# r10_0_328_1284.net
KiCad netlist of a schematic drawn in EAGLE
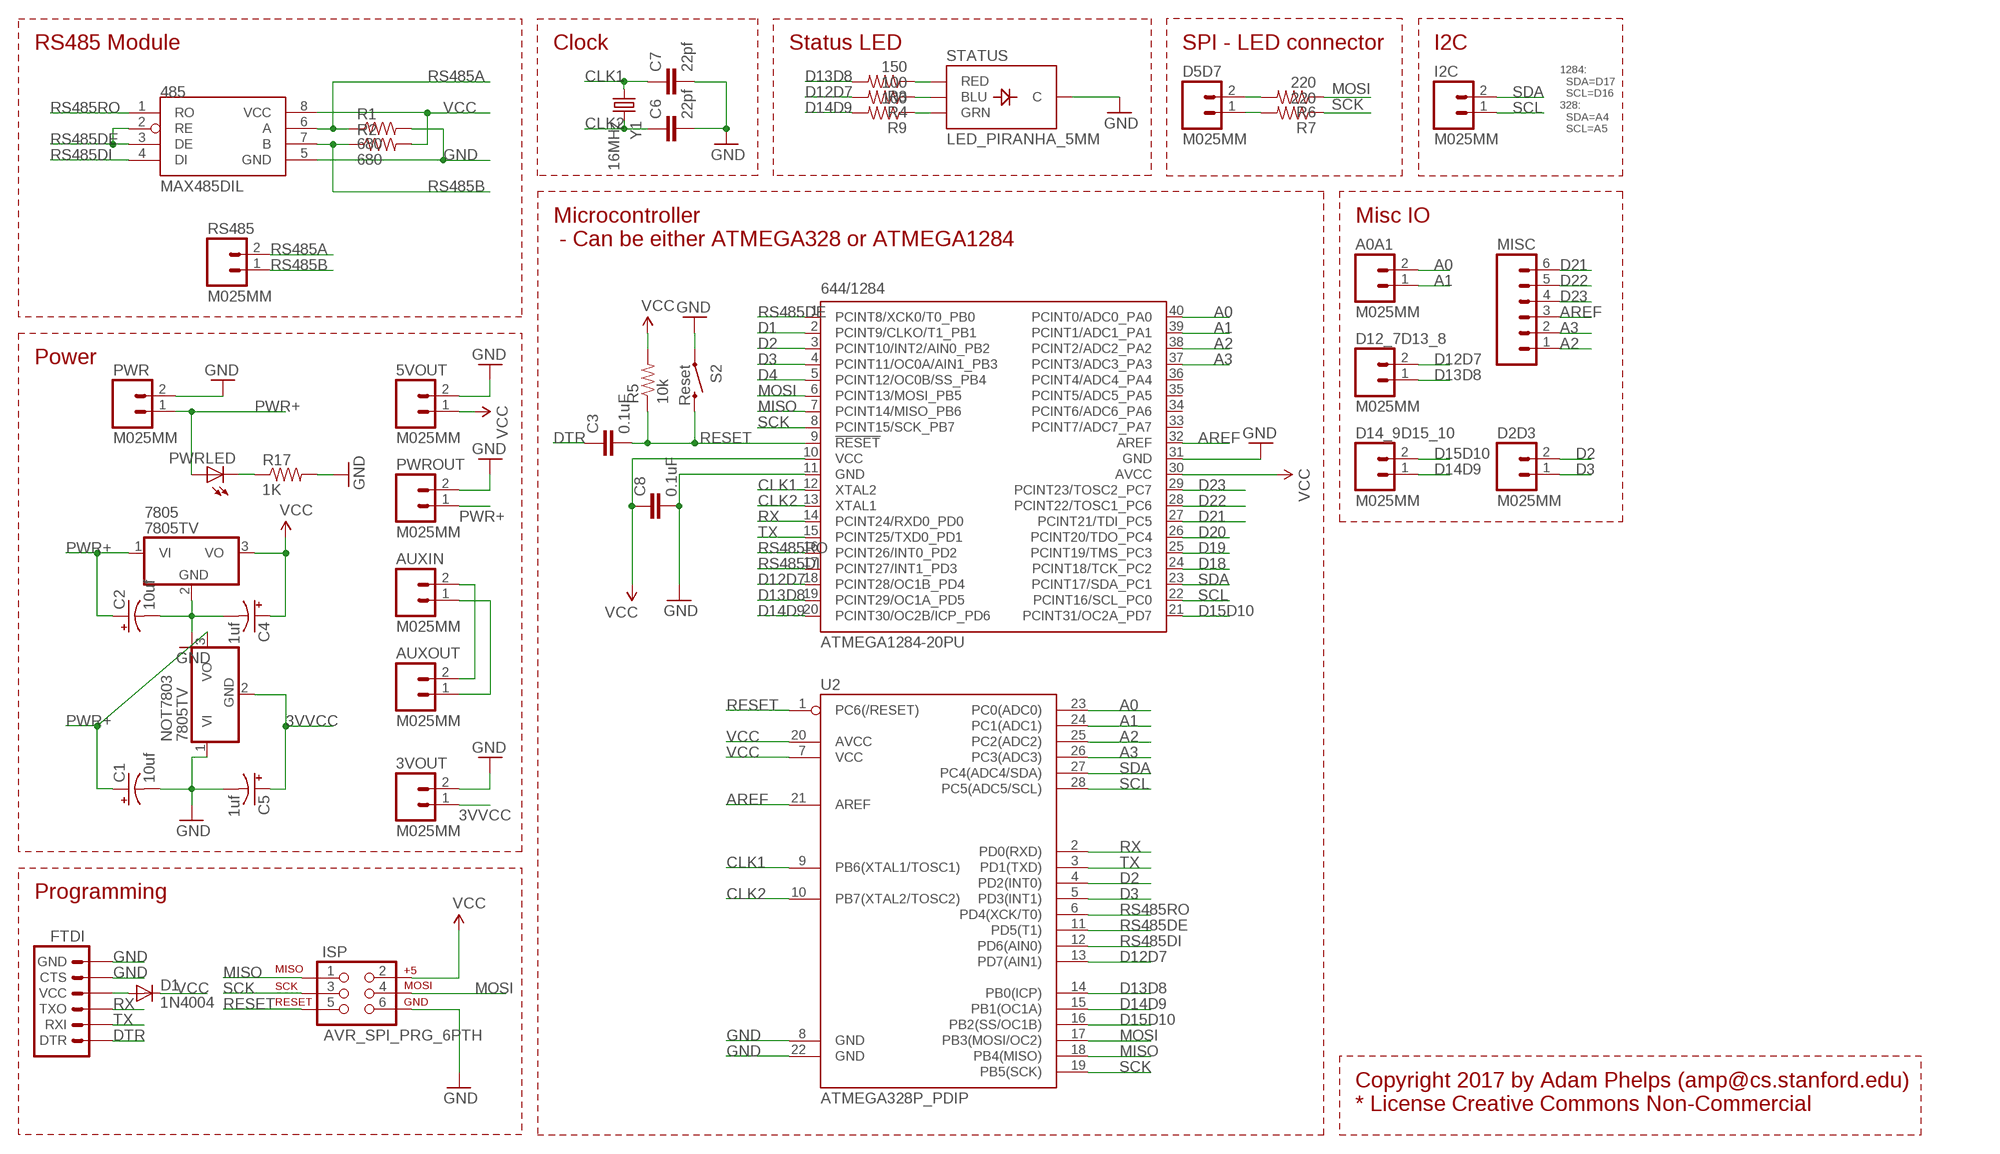
[diagram p0: schematic, sheet 1]

(export (version "E")
  (design (tool "Eeschema 10.0.6"))
  (components
    (comp (ref "3VOUT")
      (value "M025MM")
      (footprint "eagle-import:SCREWTERMINAL-5MM-2")
      (libsource (lib "eagle-import") (part "M025MM"))
    )
    (comp (ref "5VOUT")
      (value "M025MM")
      (footprint "eagle-import:SCREWTERMINAL-5MM-2")
      (libsource (lib "eagle-import") (part "M025MM"))
    )
    (comp (ref "485")
      (value "MAX485DIL")
      (footprint "eagle-import:DIL08")
      (libsource (lib "eagle-import") (part "MAX485DIL"))
    )
    (comp (ref "644/1284")
      (value "ATMEGA1284-20PU")
      (footprint "eagle-import:DIL40")
      (fields (field (name "MPN") "ATMEGA644-20PU"))
      (libsource (lib "eagle-import") (part "ATMEGA644-PU20"))
    )
    (comp (ref "7805")
      (value "7805TV")
      (footprint "eagle-import:TO220V")
      (libsource (lib "eagle-import") (part "78TV05"))
    )
    (comp (ref "A0A1")
      (value "M025MM")
      (footprint "eagle-import:SCREWTERMINAL-5MM-2")
      (libsource (lib "eagle-import") (part "M025MM"))
    )
    (comp (ref "AUXIN")
      (value "M025MM")
      (footprint "eagle-import:SCREWTERMINAL-5MM-2")
      (libsource (lib "eagle-import") (part "M025MM"))
    )
    (comp (ref "AUXOUT")
      (value "M025MM")
      (footprint "eagle-import:SCREWTERMINAL-5MM-2")
      (libsource (lib "eagle-import") (part "M025MM"))
    )
    (comp (ref "C1")
      (value "10uf")
      (footprint "eagle-import:CPOL-RADIAL-10UF-25V")
      (libsource (lib "eagle-import") (part "CAP_POLPTH2"))
    )
    (comp (ref "C2")
      (value "10uf")
      (footprint "eagle-import:CPOL-RADIAL-10UF-25V")
      (libsource (lib "eagle-import") (part "CAP_POLPTH2"))
    )
    (comp (ref "C3")
      (value "0.1uF")
      (footprint "eagle-import:CAP-PTH-SMALL")
      (libsource (lib "eagle-import") (part "CAPPTH"))
    )
    (comp (ref "C4")
      (value "1uf")
      (footprint "eagle-import:CPOL-RADIAL-10UF-25V")
      (libsource (lib "eagle-import") (part "CAP_POLPTH2"))
    )
    (comp (ref "C5")
      (value "1uf")
      (footprint "eagle-import:CPOL-RADIAL-10UF-25V")
      (libsource (lib "eagle-import") (part "CAP_POLPTH2"))
    )
    (comp (ref "C6")
      (value "22pf")
      (footprint "eagle-import:CAP-PTH-SMALL")
      (libsource (lib "eagle-import") (part "CAPPTH"))
    )
    (comp (ref "C7")
      (value "22pf")
      (footprint "eagle-import:CAP-PTH-SMALL")
      (libsource (lib "eagle-import") (part "CAPPTH"))
    )
    (comp (ref "C8")
      (value "0.1uF")
      (footprint "eagle-import:CAP-PTH-SMALL")
      (libsource (lib "eagle-import") (part "CAPPTH"))
    )
    (comp (ref "D1")
      (value "1N4004")
      (footprint "eagle-import:DO41-10")
      (libsource (lib "eagle-import") (part "1N4004"))
    )
    (comp (ref "D2D3")
      (value "M025MM")
      (footprint "eagle-import:SCREWTERMINAL-5MM-2")
      (libsource (lib "eagle-import") (part "M025MM"))
    )
    (comp (ref "D5D7")
      (value "M025MM")
      (footprint "eagle-import:SCREWTERMINAL-5MM-2")
      (libsource (lib "eagle-import") (part "M025MM"))
    )
    (comp (ref "D12_7D13_8")
      (value "M025MM")
      (footprint "eagle-import:SCREWTERMINAL-5MM-2")
      (libsource (lib "eagle-import") (part "M025MM"))
    )
    (comp (ref "D14_9D15_10")
      (value "M025MM")
      (footprint "eagle-import:SCREWTERMINAL-5MM-2")
      (libsource (lib "eagle-import") (part "M025MM"))
    )
    (comp (ref "FTDI")
      (value "ARDUINO_SERIAL_PROGRAMPTH")
      (footprint "eagle-import:1X06")
      (libsource (lib "eagle-import") (part "ARDUINO_SERIAL_PROGRAMPTH"))
    )
    (comp (ref "I2C")
      (value "M025MM")
      (footprint "eagle-import:SCREWTERMINAL-5MM-2")
      (libsource (lib "eagle-import") (part "M025MM"))
    )
    (comp (ref "ISP")
      (value "AVR_SPI_PRG_6PTH")
      (footprint "eagle-import:2X3")
      (libsource (lib "eagle-import") (part "AVR_SPI_PRG_6PTH"))
    )
    (comp (ref "MISC")
      (value "M06NO_SILK")
      (footprint "eagle-import:1X06_NO_SILK")
      (libsource (lib "eagle-import") (part "M06NO_SILK"))
    )
    (comp (ref "NOT7803")
      (value "7805TV")
      (footprint "eagle-import:TO220V")
      (libsource (lib "eagle-import") (part "78TV05"))
    )
    (comp (ref "PWR")
      (value "M025MM")
      (footprint "eagle-import:SCREWTERMINAL-5MM-2")
      (libsource (lib "eagle-import") (part "M025MM"))
    )
    (comp (ref "PWRLED")
      (value "LED5MM")
      (footprint "eagle-import:LED5MM")
      (libsource (lib "eagle-import") (part "LED5MM"))
    )
    (comp (ref "PWROUT")
      (value "M025MM")
      (footprint "eagle-import:SCREWTERMINAL-5MM-2")
      (libsource (lib "eagle-import") (part "M025MM"))
    )
    (comp (ref "R1")
      (value "680")
      (footprint "eagle-import:AXIAL-0.4")
      (libsource (lib "eagle-import") (part "SparkFun-Resistors_RESISTORPTH-1/4W"))
    )
    (comp (ref "R2")
      (value "680")
      (footprint "eagle-import:AXIAL-0.4")
      (libsource (lib "eagle-import") (part "SparkFun-Resistors_RESISTORPTH-1/4W"))
    )
    (comp (ref "R3")
      (value "150")
      (footprint "eagle-import:AXIAL-0.4")
      (libsource (lib "eagle-import") (part "RESISTORPTH-1/4W"))
    )
    (comp (ref "R4")
      (value "100")
      (footprint "eagle-import:AXIAL-0.4")
      (libsource (lib "eagle-import") (part "RESISTORPTH-1/4W"))
    )
    (comp (ref "R5")
      (value "10k")
      (footprint "eagle-import:AXIAL-0.4")
      (libsource (lib "eagle-import") (part "RESISTORPTH-1/4W"))
    )
    (comp (ref "R6")
      (value "220")
      (footprint "eagle-import:AXIAL-0.4")
      (libsource (lib "eagle-import") (part "RESISTORPTH-1/4W"))
    )
    (comp (ref "R7")
      (value "220")
      (footprint "eagle-import:AXIAL-0.4")
      (libsource (lib "eagle-import") (part "RESISTORPTH-1/4W"))
    )
    (comp (ref "R9")
      (value "100")
      (footprint "eagle-import:AXIAL-0.4")
      (libsource (lib "eagle-import") (part "RESISTORPTH-1/4W"))
    )
    (comp (ref "R17")
      (value "1K")
      (footprint "eagle-import:AXIAL-0.4")
      (libsource (lib "eagle-import") (part "SparkFun-Resistors_RESISTORPTH-1/4W"))
    )
    (comp (ref "RS485")
      (value "M025MM")
      (footprint "eagle-import:SCREWTERMINAL-5MM-2")
      (libsource (lib "eagle-import") (part "M025MM"))
    )
    (comp (ref "S2")
      (value "Reset")
      (footprint "eagle-import:TACTILE_SWITCH_SMD")
      (libsource (lib "eagle-import") (part "SWITCH-MOMENTARY-2SMD"))
    )
    (comp (ref "STATUS")
      (value "LED_PIRANHA_5MM")
      (footprint "eagle-import:LED_PIRANHA_5MM")
      (libsource (lib "eagle-import") (part "LED_PIRANHA_5MM"))
    )
    (comp (ref "U2")
      (value "ATMEGA328P_PDIP")
      (footprint "eagle-import:DIL28-3")
      (libsource (lib "eagle-import") (part "ATMEGA328P_PDIP"))
    )
    (comp (ref "Y1")
      (value "16MHz")
      (footprint "eagle-import:HC49US")
      (libsource (lib "eagle-import") (part "CRYSTALHC49US"))
    )
  )
  (nets
    (net (code "1") (name "/3VVCC") (class "Default")
      (node (ref "3VOUT") (pin "1") (pinfunction "1_1") (pintype "passive"))
      (node (ref "C5") (pin "1") (pinfunction "+_1") (pintype "passive"))
      (node (ref "NOT7803") (pin "2") (pinfunction "GND_2") (pintype "passive"))
    )
    (net (code "2") (name "/A0") (class "Default")
      (node (ref "644/1284") (pin "40") (pinfunction "PCINT0/ADC0_PA0_40") (pintype "bidirectional"))
      (node (ref "A0A1") (pin "2") (pinfunction "2_2") (pintype "passive"))
      (node (ref "U2") (pin "23") (pinfunction "PC0(ADC0)_23") (pintype "bidirectional"))
    )
    (net (code "3") (name "/A1") (class "Default")
      (node (ref "644/1284") (pin "39") (pinfunction "PCINT1/ADC1_PA1_39") (pintype "bidirectional"))
      (node (ref "A0A1") (pin "1") (pinfunction "1_1") (pintype "passive"))
      (node (ref "U2") (pin "24") (pinfunction "PC1(ADC1)_24") (pintype "bidirectional"))
    )
    (net (code "4") (name "/A2") (class "Default")
      (node (ref "644/1284") (pin "38") (pinfunction "PCINT2/ADC2_PA2_38") (pintype "bidirectional"))
      (node (ref "MISC") (pin "1") (pinfunction "1_1") (pintype "passive"))
      (node (ref "U2") (pin "25") (pinfunction "PC2(ADC2)_25") (pintype "bidirectional"))
    )
    (net (code "5") (name "/A3") (class "Default")
      (node (ref "644/1284") (pin "37") (pinfunction "PCINT3/ADC3_PA3_37") (pintype "bidirectional"))
      (node (ref "MISC") (pin "2") (pinfunction "2_2") (pintype "passive"))
      (node (ref "U2") (pin "26") (pinfunction "PC3(ADC3)_26") (pintype "bidirectional"))
    )
    (net (code "6") (name "/AREF") (class "Default")
      (node (ref "644/1284") (pin "32") (pinfunction "AREF_32") (pintype "passive"))
      (node (ref "MISC") (pin "3") (pinfunction "3_3") (pintype "passive"))
      (node (ref "U2") (pin "21") (pinfunction "AREF_21") (pintype "bidirectional"))
    )
    (net (code "7") (name "/CLK1") (class "Default")
      (node (ref "644/1284") (pin "12") (pinfunction "XTAL2_12") (pintype "output"))
      (node (ref "C7") (pin "1") (pinfunction "1_1") (pintype "passive"))
      (node (ref "U2") (pin "9") (pinfunction "PB6(XTAL1/TOSC1)_9") (pintype "bidirectional"))
      (node (ref "Y1") (pin "1") (pinfunction "1_1") (pintype "passive"))
    )
    (net (code "8") (name "/CLK2") (class "Default")
      (node (ref "644/1284") (pin "13") (pinfunction "XTAL1_13") (pintype "input"))
      (node (ref "C6") (pin "1") (pinfunction "1_1") (pintype "passive"))
      (node (ref "U2") (pin "10") (pinfunction "PB7(XTAL2/TOSC2)_10") (pintype "bidirectional"))
      (node (ref "Y1") (pin "2") (pinfunction "2_2") (pintype "passive"))
    )
    (net (code "9") (name "/D1") (class "Default")
      (node (ref "644/1284") (pin "2") (pinfunction "PCINT9/CLKO/T1_PB1_2") (pintype "bidirectional"))
    )
    (net (code "10") (name "/D2") (class "Default")
      (node (ref "644/1284") (pin "3") (pinfunction "PCINT10/INT2/AIN0_PB2_3") (pintype "bidirectional"))
      (node (ref "D2D3") (pin "2") (pinfunction "2_2") (pintype "passive"))
      (node (ref "U2") (pin "4") (pinfunction "PD2(INT0)_4") (pintype "bidirectional"))
    )
    (net (code "11") (name "/D3") (class "Default")
      (node (ref "644/1284") (pin "4") (pinfunction "PCINT11/OC0A/AIN1_PB3_4") (pintype "bidirectional"))
      (node (ref "D2D3") (pin "1") (pinfunction "1_1") (pintype "passive"))
      (node (ref "U2") (pin "5") (pinfunction "PD3(INT1)_5") (pintype "bidirectional"))
    )
    (net (code "12") (name "/D4") (class "Default")
      (node (ref "644/1284") (pin "5") (pinfunction "PCINT12/OC0B/SS_PB4_5") (pintype "bidirectional"))
    )
    (net (code "13") (name "/D12D7") (class "Default")
      (node (ref "644/1284") (pin "18") (pinfunction "PCINT28/OC1B_PD4_18") (pintype "bidirectional"))
      (node (ref "D12_7D13_8") (pin "2") (pinfunction "2_2") (pintype "passive"))
      (node (ref "R4") (pin "P$2") (pinfunction "2_P$2") (pintype "passive"))
      (node (ref "U2") (pin "13") (pinfunction "PD7(AIN1)_13") (pintype "bidirectional"))
    )
    (net (code "14") (name "/D13D8") (class "Default")
      (node (ref "644/1284") (pin "19") (pinfunction "PCINT29/OC1A_PD5_19") (pintype "bidirectional"))
      (node (ref "D12_7D13_8") (pin "1") (pinfunction "1_1") (pintype "passive"))
      (node (ref "R3") (pin "P$2") (pinfunction "2_P$2") (pintype "passive"))
      (node (ref "U2") (pin "14") (pinfunction "PB0(ICP)_14") (pintype "bidirectional"))
    )
    (net (code "15") (name "/D14D9") (class "Default")
      (node (ref "644/1284") (pin "20") (pinfunction "PCINT30/OC2B/ICP_PD6_20") (pintype "bidirectional"))
      (node (ref "D14_9D15_10") (pin "1") (pinfunction "1_1") (pintype "passive"))
      (node (ref "R9") (pin "P$2") (pinfunction "2_P$2") (pintype "passive"))
      (node (ref "U2") (pin "15") (pinfunction "PB1(OC1A)_15") (pintype "bidirectional"))
    )
    (net (code "16") (name "/D15D10") (class "Default")
      (node (ref "644/1284") (pin "21") (pinfunction "PCINT31/OC2A_PD7_21") (pintype "bidirectional"))
      (node (ref "D14_9D15_10") (pin "2") (pinfunction "2_2") (pintype "passive"))
      (node (ref "U2") (pin "16") (pinfunction "PB2(SS/OC1B)_16") (pintype "bidirectional"))
    )
    (net (code "17") (name "/D18") (class "Default")
      (node (ref "644/1284") (pin "24") (pinfunction "PCINT18/TCK_PC2_24") (pintype "bidirectional"))
    )
    (net (code "18") (name "/D19") (class "Default")
      (node (ref "644/1284") (pin "25") (pinfunction "PCINT19/TMS_PC3_25") (pintype "bidirectional"))
    )
    (net (code "19") (name "/D20") (class "Default")
      (node (ref "644/1284") (pin "26") (pinfunction "PCINT20/TDO_PC4_26") (pintype "bidirectional"))
    )
    (net (code "20") (name "/D21") (class "Default")
      (node (ref "644/1284") (pin "27") (pinfunction "PCINT21/TDI_PC5_27") (pintype "bidirectional"))
      (node (ref "MISC") (pin "6") (pinfunction "6_6") (pintype "passive"))
    )
    (net (code "21") (name "/D22") (class "Default")
      (node (ref "644/1284") (pin "28") (pinfunction "PCINT22/TOSC1_PC6_28") (pintype "bidirectional"))
      (node (ref "MISC") (pin "5") (pinfunction "5_5") (pintype "passive"))
    )
    (net (code "22") (name "/D23") (class "Default")
      (node (ref "644/1284") (pin "29") (pinfunction "PCINT23/TOSC2_PC7_29") (pintype "bidirectional"))
      (node (ref "MISC") (pin "4") (pinfunction "4_4") (pintype "passive"))
    )
    (net (code "23") (name "/DTR") (class "Default")
      (node (ref "C3") (pin "1") (pinfunction "1_1") (pintype "passive"))
      (node (ref "FTDI") (pin "DTR") (pinfunction "DTR_DTR") (pintype "passive"))
    )
    (net (code "24") (name "/MISO") (class "Default")
      (node (ref "644/1284") (pin "7") (pinfunction "PCINT14/MISO_PB6_7") (pintype "bidirectional"))
      (node (ref "ISP") (pin "1") (pinfunction "1_1") (pintype "passive"))
      (node (ref "U2") (pin "18") (pinfunction "PB4(MISO)_18") (pintype "bidirectional"))
    )
    (net (code "25") (name "/MOSI") (class "Default")
      (node (ref "644/1284") (pin "6") (pinfunction "PCINT13/MOSI_PB5_6") (pintype "bidirectional"))
      (node (ref "ISP") (pin "4") (pinfunction "4_4") (pintype "passive"))
      (node (ref "R6") (pin "P$1") (pinfunction "1_P$1") (pintype "passive"))
      (node (ref "U2") (pin "17") (pinfunction "PB3(MOSI/OC2)_17") (pintype "bidirectional"))
    )
    (net (code "26") (name "/PWR+") (class "Default")
      (node (ref "7805") (pin "1") (pinfunction "VI_1") (pintype "input"))
      (node (ref "C1") (pin "1") (pinfunction "+_1") (pintype "passive"))
      (node (ref "C2") (pin "1") (pinfunction "+_1") (pintype "passive"))
      (node (ref "NOT7803") (pin "3") (pinfunction "VO_3") (pintype "passive"))
      (node (ref "PWR") (pin "1") (pinfunction "1_1") (pintype "passive"))
      (node (ref "PWRLED") (pin "A") (pinfunction "A_A") (pintype "passive"))
      (node (ref "PWROUT") (pin "1") (pinfunction "1_1") (pintype "passive"))
    )
    (net (code "27") (name "/RESET") (class "Default")
      (node (ref "644/1284") (pin "9") (pinfunction "~{RESET}_9") (pintype "input"))
      (node (ref "C3") (pin "2") (pinfunction "2_2") (pintype "passive"))
      (node (ref "ISP") (pin "5") (pinfunction "5_5") (pintype "passive"))
      (node (ref "R5") (pin "P$1") (pinfunction "1_P$1") (pintype "passive"))
      (node (ref "S2") (pin "3") (pinfunction "2_3") (pintype "passive"))
      (node (ref "U2") (pin "1") (pinfunction "PC6(/RESET)_1") (pintype "bidirectional"))
    )
    (net (code "28") (name "/RS485A") (class "Default")
      (node (ref "485") (pin "6") (pinfunction "A_6") (pintype "bidirectional"))
      (node (ref "R1") (pin "P$1") (pinfunction "1_P$1") (pintype "passive"))
      (node (ref "RS485") (pin "2") (pinfunction "2_2") (pintype "passive"))
    )
    (net (code "29") (name "/RS485B") (class "Default")
      (node (ref "485") (pin "7") (pinfunction "B_7") (pintype "bidirectional"))
      (node (ref "R2") (pin "P$1") (pinfunction "1_P$1") (pintype "passive"))
      (node (ref "RS485") (pin "1") (pinfunction "1_1") (pintype "passive"))
    )
    (net (code "30") (name "/RS485DE") (class "Default")
      (node (ref "485") (pin "2") (pinfunction "RE_2") (pintype "bidirectional"))
      (node (ref "485") (pin "3") (pinfunction "DE_3") (pintype "bidirectional"))
      (node (ref "644/1284") (pin "1") (pinfunction "PCINT8/XCK0/T0_PB0_1") (pintype "bidirectional"))
      (node (ref "U2") (pin "11") (pinfunction "PD5(T1)_11") (pintype "bidirectional"))
    )
    (net (code "31") (name "/RS485DI") (class "Default")
      (node (ref "485") (pin "4") (pinfunction "DI_4") (pintype "bidirectional"))
      (node (ref "644/1284") (pin "17") (pinfunction "PCINT27/INT1_PD3_17") (pintype "bidirectional"))
      (node (ref "U2") (pin "12") (pinfunction "PD6(AIN0)_12") (pintype "bidirectional"))
    )
    (net (code "32") (name "/RS485RO") (class "Default")
      (node (ref "485") (pin "1") (pinfunction "RO_1") (pintype "bidirectional"))
      (node (ref "644/1284") (pin "16") (pinfunction "PCINT26/INT0_PD2_16") (pintype "bidirectional"))
      (node (ref "U2") (pin "6") (pinfunction "PD4(XCK/T0)_6") (pintype "bidirectional"))
    )
    (net (code "33") (name "/RX") (class "Default")
      (node (ref "644/1284") (pin "14") (pinfunction "PCINT24/RXD0_PD0_14") (pintype "bidirectional"))
      (node (ref "FTDI") (pin "TXO") (pinfunction "TXO_TXO") (pintype "passive"))
      (node (ref "U2") (pin "2") (pinfunction "PD0(RXD)_2") (pintype "bidirectional"))
    )
    (net (code "34") (name "/SCK") (class "Default")
      (node (ref "644/1284") (pin "8") (pinfunction "PCINT15/SCK_PB7_8") (pintype "bidirectional"))
      (node (ref "ISP") (pin "3") (pinfunction "3_3") (pintype "passive"))
      (node (ref "R7") (pin "P$1") (pinfunction "1_P$1") (pintype "passive"))
      (node (ref "U2") (pin "19") (pinfunction "PB5(SCK)_19") (pintype "bidirectional"))
    )
    (net (code "35") (name "/SCL") (class "Default")
      (node (ref "644/1284") (pin "22") (pinfunction "PCINT16/SCL_PC0_22") (pintype "bidirectional"))
      (node (ref "I2C") (pin "1") (pinfunction "1_1") (pintype "passive"))
      (node (ref "U2") (pin "28") (pinfunction "PC5(ADC5/SCL)_28") (pintype "bidirectional"))
    )
    (net (code "36") (name "/SDA") (class "Default")
      (node (ref "644/1284") (pin "23") (pinfunction "PCINT17/SDA_PC1_23") (pintype "bidirectional"))
      (node (ref "I2C") (pin "2") (pinfunction "2_2") (pintype "passive"))
      (node (ref "U2") (pin "27") (pinfunction "PC4(ADC4/SDA)_27") (pintype "bidirectional"))
    )
    (net (code "37") (name "/TX") (class "Default")
      (node (ref "644/1284") (pin "15") (pinfunction "PCINT25/TXD0_PD1_15") (pintype "bidirectional"))
      (node (ref "FTDI") (pin "RXI") (pinfunction "RXI_RXI") (pintype "passive"))
      (node (ref "U2") (pin "3") (pinfunction "PD1(TXD)_3") (pintype "bidirectional"))
    )
    (net (code "38") (name "GND") (class "Default")
      (node (ref "3VOUT") (pin "2") (pinfunction "2_2") (pintype "passive"))
      (node (ref "485") (pin "5") (pinfunction "GND_5") (pintype "bidirectional"))
      (node (ref "5VOUT") (pin "2") (pinfunction "2_2") (pintype "passive"))
      (node (ref "644/1284") (pin "11") (pinfunction "GND_11") (pintype "power_in"))
      (node (ref "644/1284") (pin "31") (pinfunction "GND_31") (pintype "power_in"))
      (node (ref "7805") (pin "2") (pinfunction "GND_2") (pintype "passive"))
      (node (ref "C1") (pin "2") (pinfunction "-_2") (pintype "passive"))
      (node (ref "C2") (pin "2") (pinfunction "-_2") (pintype "passive"))
      (node (ref "C4") (pin "2") (pinfunction "-_2") (pintype "passive"))
      (node (ref "C5") (pin "2") (pinfunction "-_2") (pintype "passive"))
      (node (ref "C6") (pin "2") (pinfunction "2_2") (pintype "passive"))
      (node (ref "C7") (pin "2") (pinfunction "2_2") (pintype "passive"))
      (node (ref "C8") (pin "2") (pinfunction "2_2") (pintype "passive"))
      (node (ref "FTDI") (pin "CTS") (pinfunction "CTS_CTS") (pintype "passive"))
      (node (ref "FTDI") (pin "GND") (pinfunction "GND_GND") (pintype "passive"))
      (node (ref "ISP") (pin "6") (pinfunction "6_6") (pintype "passive"))
      (node (ref "NOT7803") (pin "1") (pinfunction "VI_1") (pintype "input"))
      (node (ref "PWR") (pin "2") (pinfunction "2_2") (pintype "passive"))
      (node (ref "PWROUT") (pin "2") (pinfunction "2_2") (pintype "passive"))
      (node (ref "R1") (pin "P$2") (pinfunction "2_P$2") (pintype "passive"))
      (node (ref "R17") (pin "P$2") (pinfunction "2_P$2") (pintype "passive"))
      (node (ref "S2") (pin "1") (pinfunction "1_1") (pintype "passive"))
      (node (ref "STATUS") (pin "-") (pinfunction "C_-") (pintype "bidirectional"))
      (node (ref "U2") (pin "22") (pinfunction "GND_22") (pintype "bidirectional"))
      (node (ref "U2") (pin "8") (pinfunction "GND_8") (pintype "bidirectional"))
    )
    (net (code "39") (name "Net-(AUXIN-Pad1)") (class "Default")
      (node (ref "AUXIN") (pin "1") (pinfunction "1_1") (pintype "passive"))
      (node (ref "AUXOUT") (pin "1") (pinfunction "1_1") (pintype "passive"))
    )
    (net (code "40") (name "Net-(AUXIN-Pad2)") (class "Default")
      (node (ref "AUXIN") (pin "2") (pinfunction "2_2") (pintype "passive"))
      (node (ref "AUXOUT") (pin "2") (pinfunction "2_2") (pintype "passive"))
    )
    (net (code "41") (name "Net-(D1-PadA)") (class "Default")
      (node (ref "D1") (pin "A") (pinfunction "A_A") (pintype "passive"))
      (node (ref "FTDI") (pin "VCC") (pinfunction "VCC_VCC") (pintype "passive"))
    )
    (net (code "42") (name "Net-(PWRLED-C)") (class "Default")
      (node (ref "PWRLED") (pin "K") (pinfunction "C_K") (pintype "passive"))
      (node (ref "R17") (pin "P$1") (pinfunction "1_P$1") (pintype "passive"))
    )
    (net (code "43") (name "Net-(R3-1)") (class "Default")
      (node (ref "R3") (pin "P$1") (pinfunction "1_P$1") (pintype "passive"))
      (node (ref "STATUS") (pin "R") (pinfunction "RED_R") (pintype "bidirectional"))
    )
    (net (code "44") (name "Net-(R4-1)") (class "Default")
      (node (ref "R4") (pin "P$1") (pinfunction "1_P$1") (pintype "passive"))
      (node (ref "STATUS") (pin "B") (pinfunction "BLU_B") (pintype "bidirectional"))
    )
    (net (code "45") (name "Net-(R6-2)") (class "Default")
      (node (ref "D5D7") (pin "2") (pinfunction "2_2") (pintype "passive"))
      (node (ref "R6") (pin "P$2") (pinfunction "2_P$2") (pintype "passive"))
    )
    (net (code "46") (name "Net-(R7-2)") (class "Default")
      (node (ref "D5D7") (pin "1") (pinfunction "1_1") (pintype "passive"))
      (node (ref "R7") (pin "P$2") (pinfunction "2_P$2") (pintype "passive"))
    )
    (net (code "47") (name "Net-(R9-1)") (class "Default")
      (node (ref "R9") (pin "P$1") (pinfunction "1_P$1") (pintype "passive"))
      (node (ref "STATUS") (pin "G") (pinfunction "GRN_G") (pintype "bidirectional"))
    )
    (net (code "48") (name "VCC") (class "Default")
      (node (ref "485") (pin "8") (pinfunction "VCC_8") (pintype "bidirectional"))
      (node (ref "5VOUT") (pin "1") (pinfunction "1_1") (pintype "passive"))
      (node (ref "644/1284") (pin "10") (pinfunction "VCC_10") (pintype "power_in"))
      (node (ref "644/1284") (pin "30") (pinfunction "AVCC_30") (pintype "power_in"))
      (node (ref "7805") (pin "3") (pinfunction "VO_3") (pintype "passive"))
      (node (ref "C4") (pin "1") (pinfunction "+_1") (pintype "passive"))
      (node (ref "C8") (pin "1") (pinfunction "1_1") (pintype "passive"))
      (node (ref "D1") (pin "C") (pinfunction "C_C") (pintype "passive"))
      (node (ref "ISP") (pin "2") (pinfunction "2_2") (pintype "passive"))
      (node (ref "R2") (pin "P$2") (pinfunction "2_P$2") (pintype "passive"))
      (node (ref "R5") (pin "P$2") (pinfunction "2_P$2") (pintype "passive"))
      (node (ref "U2") (pin "20") (pinfunction "AVCC_20") (pintype "bidirectional"))
      (node (ref "U2") (pin "7") (pinfunction "VCC_7") (pintype "bidirectional"))
    )
    (net (code "49") (name "unconnected-(644/1284-PCINT4{slash}ADC4_PA4-Pad36)") (class "Default")
      (node (ref "644/1284") (pin "36") (pinfunction "PCINT4/ADC4_PA4_36") (pintype "bidirectional"))
    )
    (net (code "50") (name "unconnected-(644/1284-PCINT5{slash}ADC5_PA5-Pad35)") (class "Default")
      (node (ref "644/1284") (pin "35") (pinfunction "PCINT5/ADC5_PA5_35") (pintype "bidirectional"))
    )
    (net (code "51") (name "unconnected-(644/1284-PCINT6{slash}ADC6_PA6-Pad34)") (class "Default")
      (node (ref "644/1284") (pin "34") (pinfunction "PCINT6/ADC6_PA6_34") (pintype "bidirectional"))
    )
    (net (code "52") (name "unconnected-(644/1284-PCINT7{slash}ADC7_PA7-Pad33)") (class "Default")
      (node (ref "644/1284") (pin "33") (pinfunction "PCINT7/ADC7_PA7_33") (pintype "bidirectional"))
    )
  )
)
